# XMeter.net
KiCad netlist of a schematic drawn in Altium Designer
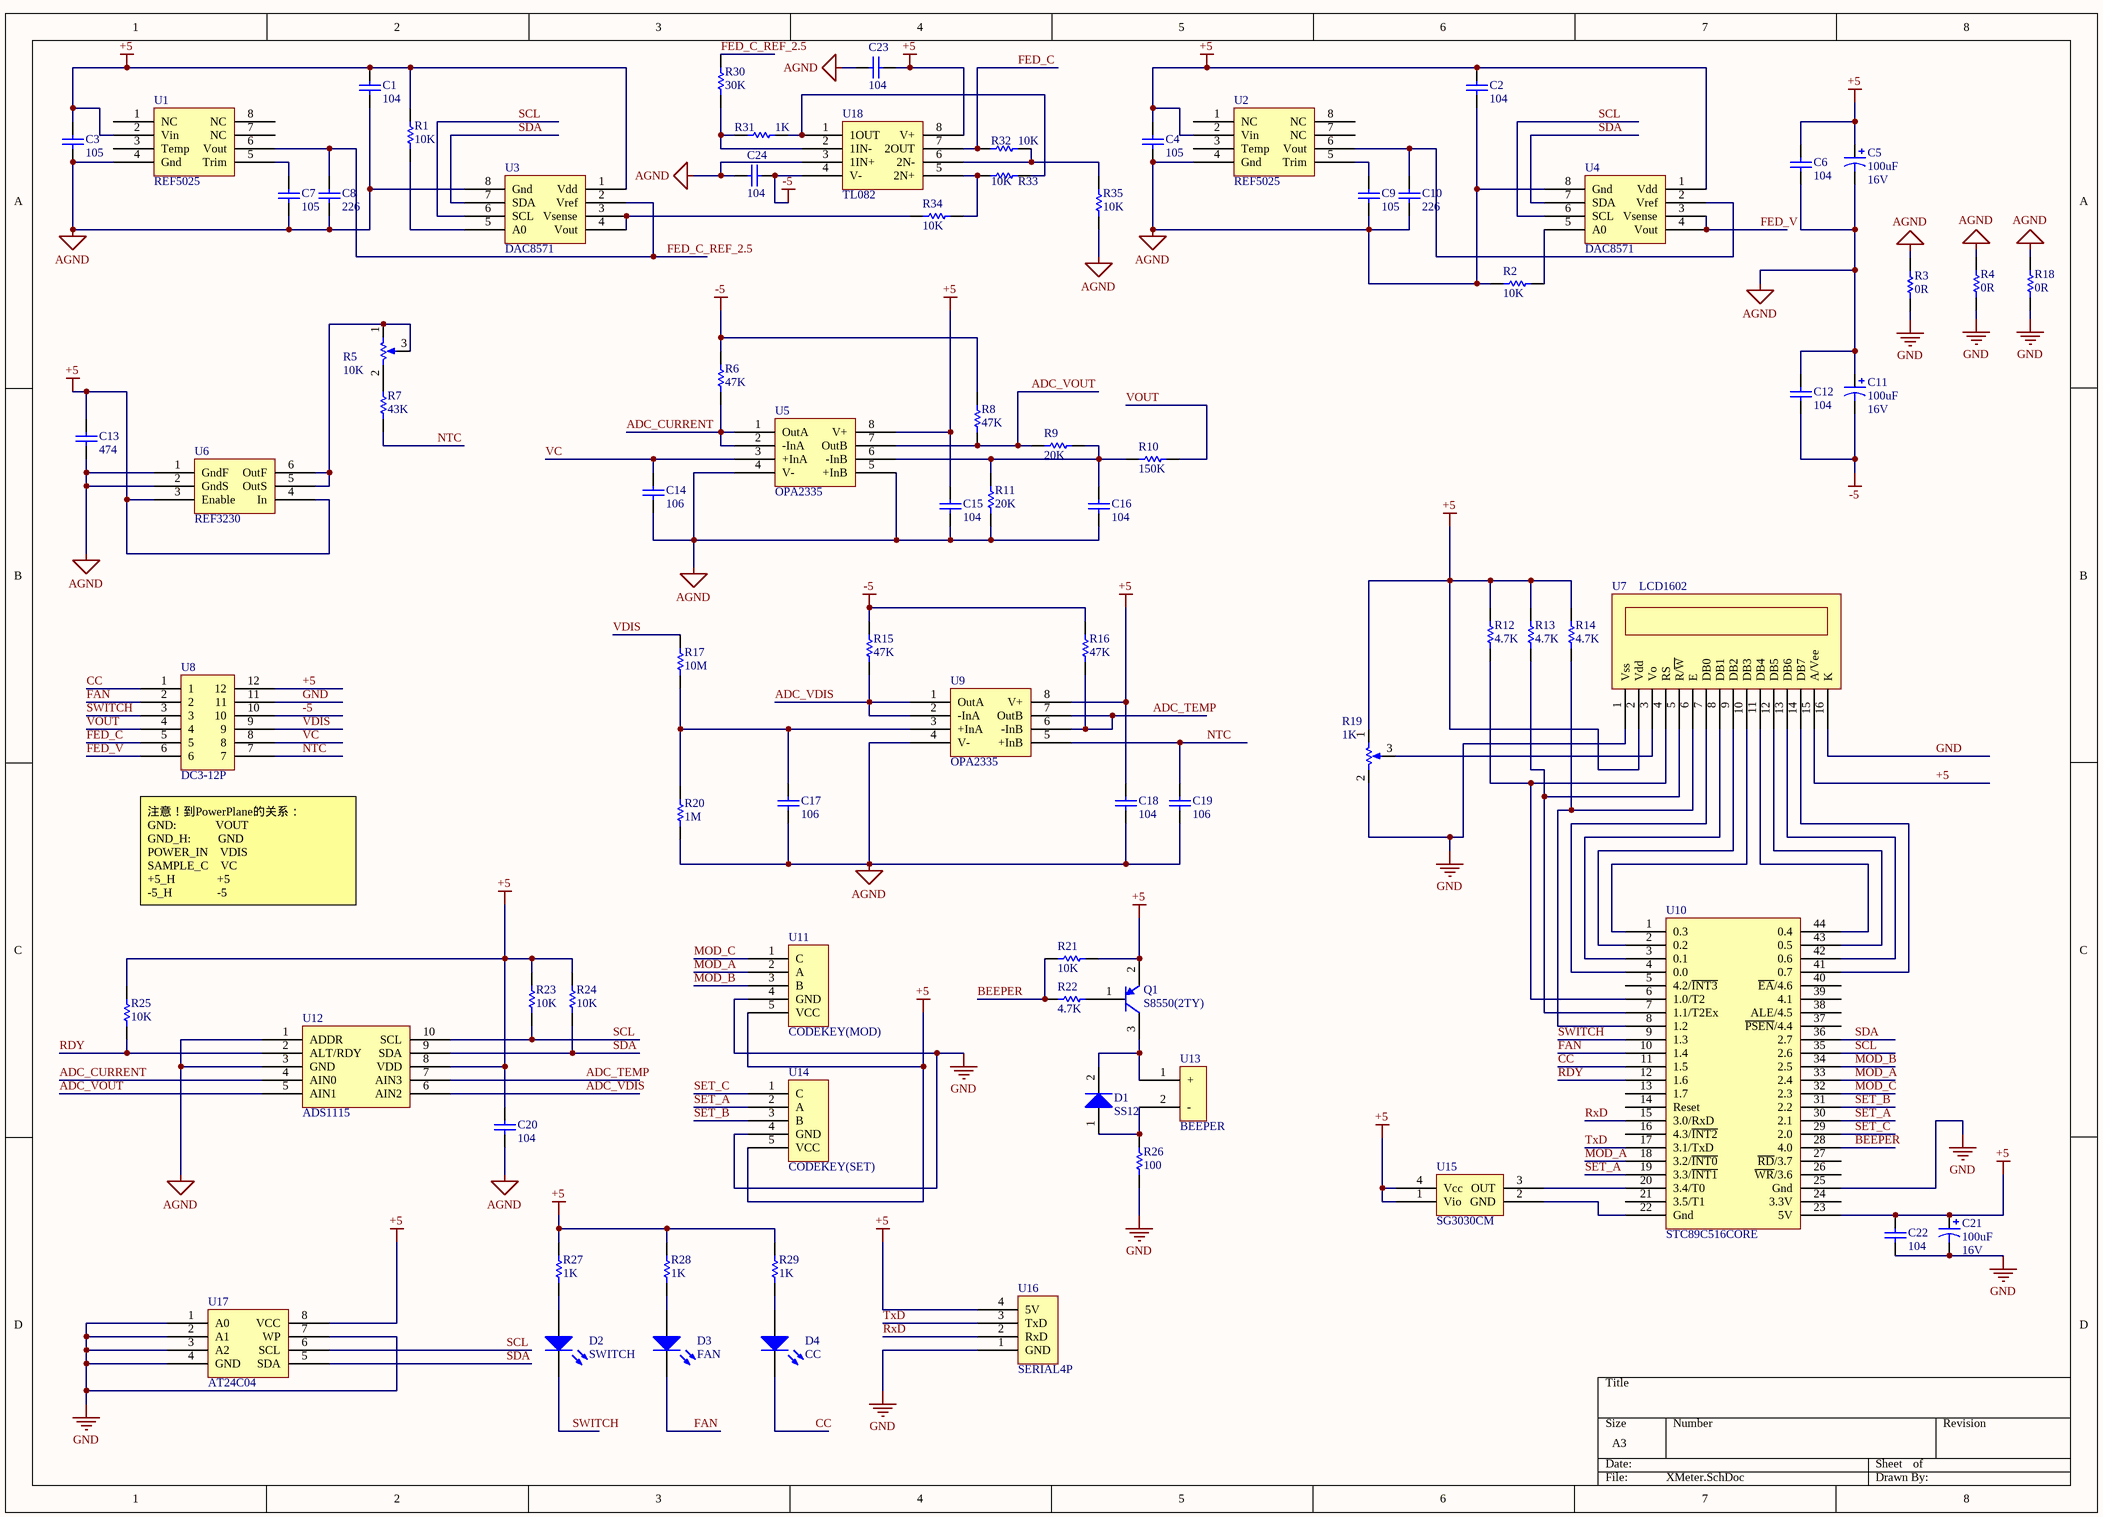
[diagram p0: XMeter.SchDoc]

(export (version "E")
  (design (tool "Eeschema 10.0.6"))
  (components
    (comp (ref "C1")
      (value "104")
      (footprint "CNCPowerSupply:CAPC1608L")
      (description "Capacitor")
      (fields (field (name "PUBLISHER") "Altium Limited"))
      (libsource (lib "Miscellaneous Devices") (part "Cap"))
    )
    (comp (ref "C2")
      (value "104")
      (footprint "CNCPowerSupply:CAPC1608L")
      (description "Capacitor")
      (fields (field (name "PUBLISHER") "Altium Limited"))
      (libsource (lib "Miscellaneous Devices") (part "Cap"))
    )
    (comp (ref "C3")
      (value "105")
      (footprint "CNCPowerSupply:CAPC1608L")
      (description "Capacitor")
      (fields (field (name "PUBLISHER") "Altium Limited"))
      (libsource (lib "Miscellaneous Devices") (part "Cap"))
    )
    (comp (ref "C4")
      (value "105")
      (footprint "CNCPowerSupply:CAPC1608L")
      (description "Capacitor")
      (fields (field (name "PUBLISHER") "Altium Limited"))
      (libsource (lib "Miscellaneous Devices") (part "Cap"))
    )
    (comp (ref "C5")
      (value "16V")
      (footprint "CNCPowerSupply:TC6032-2412")
      (description "Polarized Capacitor (Radial)")
      (fields (field (name "ALTIUM_VALUE") "100uF") (field (name "PUBLISHER") "Altium Limited"))
      (libsource (lib "Miscellaneous Devices") (part "Cap Pol1"))
    )
    (comp (ref "C6")
      (value "104")
      (footprint "CNCPowerSupply:CAPC1608L")
      (description "Capacitor")
      (fields (field (name "PUBLISHER") "Altium Limited"))
      (libsource (lib "Miscellaneous Devices") (part "Cap"))
    )
    (comp (ref "C7")
      (value "105")
      (footprint "CNCPowerSupply:CAPC1608L")
      (description "Capacitor")
      (fields (field (name "PUBLISHER") "Altium Limited"))
      (libsource (lib "Miscellaneous Devices") (part "Cap"))
    )
    (comp (ref "C8")
      (value "226")
      (footprint "CNCPowerSupply:C1206")
      (description "Capacitor")
      (fields (field (name "PUBLISHER") "Altium Limited"))
      (libsource (lib "Miscellaneous Devices") (part "Cap"))
    )
    (comp (ref "C9")
      (value "105")
      (footprint "CNCPowerSupply:CAPC1608L")
      (description "Capacitor")
      (fields (field (name "PUBLISHER") "Altium Limited"))
      (libsource (lib "Miscellaneous Devices") (part "Cap"))
    )
    (comp (ref "C10")
      (value "226")
      (footprint "CNCPowerSupply:C1206")
      (description "Capacitor")
      (fields (field (name "PUBLISHER") "Altium Limited"))
      (libsource (lib "Miscellaneous Devices") (part "Cap"))
    )
    (comp (ref "C11")
      (value "16V")
      (footprint "CNCPowerSupply:TC6032-2412")
      (description "Polarized Capacitor (Radial)")
      (fields (field (name "ALTIUM_VALUE") "100uF") (field (name "PUBLISHER") "Altium Limited"))
      (libsource (lib "Miscellaneous Devices") (part "Cap Pol1"))
    )
    (comp (ref "C12")
      (value "104")
      (footprint "CNCPowerSupply:CAPC1608L")
      (description "Capacitor")
      (fields (field (name "PUBLISHER") "Altium Limited"))
      (libsource (lib "Miscellaneous Devices") (part "Cap"))
    )
    (comp (ref "C13")
      (value "474")
      (footprint "CNCPowerSupply:CAPC1608L")
      (description "Capacitor")
      (fields (field (name "PUBLISHER") "Altium Limited"))
      (libsource (lib "Miscellaneous Devices") (part "Cap"))
    )
    (comp (ref "C14")
      (value "106")
      (footprint "CNCPowerSupply:CAPC1608L")
      (description "Capacitor")
      (fields (field (name "PUBLISHER") "Altium Limited"))
      (libsource (lib "Miscellaneous Devices") (part "Cap"))
    )
    (comp (ref "C15")
      (value "104")
      (footprint "CNCPowerSupply:CAPC1608L")
      (description "Capacitor")
      (fields (field (name "PUBLISHER") "Altium Limited"))
      (libsource (lib "Miscellaneous Devices") (part "Cap"))
    )
    (comp (ref "C16")
      (value "104")
      (footprint "CNCPowerSupply:CAPC1608L")
      (description "Capacitor")
      (fields (field (name "PUBLISHER") "Altium Limited"))
      (libsource (lib "Miscellaneous Devices") (part "Cap"))
    )
    (comp (ref "C17")
      (value "106")
      (footprint "CNCPowerSupply:CAPC1608L")
      (description "Capacitor")
      (fields (field (name "PUBLISHER") "Altium Limited"))
      (libsource (lib "Miscellaneous Devices") (part "Cap"))
    )
    (comp (ref "C18")
      (value "104")
      (footprint "CNCPowerSupply:CAPC1608L")
      (description "Capacitor")
      (fields (field (name "PUBLISHER") "Altium Limited"))
      (libsource (lib "Miscellaneous Devices") (part "Cap"))
    )
    (comp (ref "C19")
      (value "106")
      (footprint "CNCPowerSupply:CAPC1608L")
      (description "Capacitor")
      (fields (field (name "PUBLISHER") "Altium Limited"))
      (libsource (lib "Miscellaneous Devices") (part "Cap"))
    )
    (comp (ref "C20")
      (value "104")
      (footprint "CNCPowerSupply:CAPC1608L")
      (description "Capacitor")
      (fields (field (name "PUBLISHER") "Altium Limited"))
      (libsource (lib "Miscellaneous Devices") (part "Cap"))
    )
    (comp (ref "C21")
      (value "16V")
      (footprint "CNCPowerSupply:TC6032-2412")
      (description "Polarized Capacitor (Radial)")
      (fields (field (name "ALTIUM_VALUE") "100uF") (field (name "PUBLISHER") "Altium Limited"))
      (libsource (lib "Miscellaneous Devices") (part "Cap Pol1"))
    )
    (comp (ref "C22")
      (value "104")
      (footprint "CNCPowerSupply:CAPC1608L")
      (description "Capacitor")
      (fields (field (name "PUBLISHER") "Altium Limited"))
      (libsource (lib "Miscellaneous Devices") (part "Cap"))
    )
    (comp (ref "C23")
      (value "104")
      (footprint "CNCPowerSupply:CAPC1608L")
      (description "Capacitor")
      (fields (field (name "PUBLISHER") "Altium Limited"))
      (libsource (lib "Miscellaneous Devices") (part "Cap"))
    )
    (comp (ref "C24")
      (value "104")
      (footprint "CNCPowerSupply:CAPC1608L")
      (description "Capacitor")
      (fields (field (name "PUBLISHER") "Altium Limited"))
      (libsource (lib "Miscellaneous Devices") (part "Cap"))
    )
    (comp (ref "D1")
      (value "SS12")
      (footprint "CNCPowerSupply:DO214AC SMA")
      (description "1 Amp General Purpose Rectifier")
      (fields (field (name "PUBLISHER") "Altium Limited"))
      (libsource (lib "Miscellaneous Devices") (part "Diode 1N4007"))
    )
    (comp (ref "D2")
      (value "SWITCH")
      (footprint "CNCPowerSupply:LED")
      (description "Typical RED GaAs LED")
      (fields (field (name "PUBLISHER") "Altium Limited"))
      (libsource (lib "Miscellaneous Devices") (part "LED1"))
    )
    (comp (ref "D3")
      (value "FAN")
      (footprint "CNCPowerSupply:LED")
      (description "Typical RED GaAs LED")
      (fields (field (name "PUBLISHER") "Altium Limited"))
      (libsource (lib "Miscellaneous Devices") (part "LED1"))
    )
    (comp (ref "D4")
      (value "CC")
      (footprint "CNCPowerSupply:LED")
      (description "Typical RED GaAs LED")
      (fields (field (name "PUBLISHER") "Altium Limited"))
      (libsource (lib "Miscellaneous Devices") (part "LED1"))
    )
    (comp (ref "Q1")
      (value "S8550(2TY)")
      (footprint "CNCPowerSupply:SOT-23B_L")
      (description "PNP Bipolar Transistor")
      (fields (field (name "PUBLISHER") "Altium Limited"))
      (libsource (lib "Miscellaneous Devices") (part "PNP"))
    )
    (comp (ref "R1")
      (value "10K")
      (footprint "CNCPowerSupply:RESC1608L")
      (description "Resistor")
      (fields (field (name "PUBLISHER") "Altium Limited"))
      (libsource (lib "Miscellaneous Devices") (part "Res1"))
    )
    (comp (ref "R2")
      (value "10K")
      (footprint "CNCPowerSupply:RESC1608L")
      (description "Resistor")
      (fields (field (name "PUBLISHER") "Altium Limited"))
      (libsource (lib "Miscellaneous Devices") (part "Res1"))
    )
    (comp (ref "R3")
      (value "0R")
      (footprint "CNCPowerSupply:RESC1608L")
      (description "Resistor")
      (fields (field (name "PUBLISHER") "Altium Limited"))
      (libsource (lib "Miscellaneous Devices") (part "Res1"))
    )
    (comp (ref "R4")
      (value "0R")
      (footprint "CNCPowerSupply:RESC1608L")
      (description "Resistor")
      (fields (field (name "PUBLISHER") "Altium Limited"))
      (libsource (lib "Miscellaneous Devices") (part "Res1"))
    )
    (comp (ref "R5")
      (value "10K")
      (footprint "CNCPowerSupply:VR5")
      (description "Potentiometer")
      (fields (field (name "PUBLISHER") "Altium Limited"))
      (libsource (lib "Miscellaneous Devices") (part "RPot"))
    )
    (comp (ref "R6")
      (value "47K")
      (footprint "CNCPowerSupply:RESC1608L")
      (description "Resistor")
      (fields (field (name "PUBLISHER") "Altium Limited"))
      (libsource (lib "Miscellaneous Devices") (part "Res1"))
    )
    (comp (ref "R7")
      (value "43K")
      (footprint "CNCPowerSupply:RESC1608L")
      (description "Resistor")
      (fields (field (name "PUBLISHER") "Altium Limited"))
      (libsource (lib "Miscellaneous Devices") (part "Res1"))
    )
    (comp (ref "R8")
      (value "47K")
      (footprint "CNCPowerSupply:RESC1608L")
      (description "Resistor")
      (fields (field (name "PUBLISHER") "Altium Limited"))
      (libsource (lib "Miscellaneous Devices") (part "Res1"))
    )
    (comp (ref "R9")
      (value "20K")
      (footprint "CNCPowerSupply:RESC1608L")
      (description "Resistor")
      (fields (field (name "PUBLISHER") "Altium Limited"))
      (libsource (lib "Miscellaneous Devices") (part "Res1"))
    )
    (comp (ref "R10")
      (value "150K")
      (footprint "CNCPowerSupply:RESC1608L")
      (description "Resistor")
      (fields (field (name "PUBLISHER") "Altium Limited"))
      (libsource (lib "Miscellaneous Devices") (part "Res1"))
    )
    (comp (ref "R11")
      (value "20K")
      (footprint "CNCPowerSupply:RESC1608L")
      (description "Resistor")
      (fields (field (name "PUBLISHER") "Altium Limited"))
      (libsource (lib "Miscellaneous Devices") (part "Res1"))
    )
    (comp (ref "R12")
      (value "4.7K")
      (footprint "CNCPowerSupply:RESC1608L")
      (description "Resistor")
      (fields (field (name "PUBLISHER") "Altium Limited"))
      (libsource (lib "Miscellaneous Devices") (part "Res1"))
    )
    (comp (ref "R13")
      (value "4.7K")
      (footprint "CNCPowerSupply:RESC1608L")
      (description "Resistor")
      (fields (field (name "PUBLISHER") "Altium Limited"))
      (libsource (lib "Miscellaneous Devices") (part "Res1"))
    )
    (comp (ref "R14")
      (value "4.7K")
      (footprint "CNCPowerSupply:RESC1608L")
      (description "Resistor")
      (fields (field (name "PUBLISHER") "Altium Limited"))
      (libsource (lib "Miscellaneous Devices") (part "Res1"))
    )
    (comp (ref "R15")
      (value "47K")
      (footprint "CNCPowerSupply:RESC1608L")
      (description "Resistor")
      (fields (field (name "PUBLISHER") "Altium Limited"))
      (libsource (lib "Miscellaneous Devices") (part "Res1"))
    )
    (comp (ref "R16")
      (value "47K")
      (footprint "CNCPowerSupply:RESC1608L")
      (description "Resistor")
      (fields (field (name "PUBLISHER") "Altium Limited"))
      (libsource (lib "Miscellaneous Devices") (part "Res1"))
    )
    (comp (ref "R17")
      (value "10M")
      (footprint "CNCPowerSupply:RESC1608L")
      (description "Resistor")
      (fields (field (name "PUBLISHER") "Altium Limited"))
      (libsource (lib "Miscellaneous Devices") (part "Res1"))
    )
    (comp (ref "R18")
      (value "0R")
      (footprint "CNCPowerSupply:RESC1608L")
      (description "Resistor")
      (fields (field (name "PUBLISHER") "Altium Limited"))
      (libsource (lib "Miscellaneous Devices") (part "Res1"))
    )
    (comp (ref "R19")
      (value "1K")
      (footprint "CNCPowerSupply:VR4")
      (description "Potentiometer")
      (fields (field (name "PUBLISHER") "Altium Limited"))
      (libsource (lib "Miscellaneous Devices") (part "RPot"))
    )
    (comp (ref "R20")
      (value "1M")
      (footprint "CNCPowerSupply:RESC1608L")
      (description "Resistor")
      (fields (field (name "PUBLISHER") "Altium Limited"))
      (libsource (lib "Miscellaneous Devices") (part "Res1"))
    )
    (comp (ref "R21")
      (value "10K")
      (footprint "CNCPowerSupply:RESC1608L")
      (description "Resistor")
      (fields (field (name "PUBLISHER") "Altium Limited"))
      (libsource (lib "Miscellaneous Devices") (part "Res1"))
    )
    (comp (ref "R22")
      (value "4.7K")
      (footprint "CNCPowerSupply:RESC1608L")
      (description "Resistor")
      (fields (field (name "PUBLISHER") "Altium Limited"))
      (libsource (lib "Miscellaneous Devices") (part "Res1"))
    )
    (comp (ref "R23")
      (value "10K")
      (footprint "CNCPowerSupply:RESC1608L")
      (description "Resistor")
      (fields (field (name "PUBLISHER") "Altium Limited"))
      (libsource (lib "Miscellaneous Devices") (part "Res1"))
    )
    (comp (ref "R24")
      (value "10K")
      (footprint "CNCPowerSupply:RESC1608L")
      (description "Resistor")
      (fields (field (name "PUBLISHER") "Altium Limited"))
      (libsource (lib "Miscellaneous Devices") (part "Res1"))
    )
    (comp (ref "R25")
      (value "10K")
      (footprint "CNCPowerSupply:RESC1608L")
      (description "Resistor")
      (fields (field (name "PUBLISHER") "Altium Limited"))
      (libsource (lib "Miscellaneous Devices") (part "Res1"))
    )
    (comp (ref "R26")
      (value "100")
      (footprint "CNCPowerSupply:RESC1608L")
      (description "Resistor")
      (fields (field (name "PUBLISHER") "Altium Limited"))
      (libsource (lib "Miscellaneous Devices") (part "Res1"))
    )
    (comp (ref "R27")
      (value "1K")
      (footprint "CNCPowerSupply:RESC1608L")
      (description "Resistor")
      (fields (field (name "PUBLISHER") "Altium Limited"))
      (libsource (lib "Miscellaneous Devices") (part "Res1"))
    )
    (comp (ref "R28")
      (value "1K")
      (footprint "CNCPowerSupply:RESC1608L")
      (description "Resistor")
      (fields (field (name "PUBLISHER") "Altium Limited"))
      (libsource (lib "Miscellaneous Devices") (part "Res1"))
    )
    (comp (ref "R29")
      (value "1K")
      (footprint "CNCPowerSupply:RESC1608L")
      (description "Resistor")
      (fields (field (name "PUBLISHER") "Altium Limited"))
      (libsource (lib "Miscellaneous Devices") (part "Res1"))
    )
    (comp (ref "R30")
      (value "30K")
      (footprint "CNCPowerSupply:RESC1608L")
      (description "Resistor")
      (fields (field (name "PUBLISHER") "Altium Limited"))
      (libsource (lib "Miscellaneous Devices") (part "Res1"))
    )
    (comp (ref "R31")
      (value "1K")
      (footprint "CNCPowerSupply:RESC1608L")
      (description "Resistor")
      (fields (field (name "PUBLISHER") "Altium Limited"))
      (libsource (lib "Miscellaneous Devices") (part "Res1"))
    )
    (comp (ref "R32")
      (value "10K")
      (footprint "CNCPowerSupply:RESC1608L")
      (description "Resistor")
      (fields (field (name "PUBLISHER") "Altium Limited"))
      (libsource (lib "Miscellaneous Devices") (part "Res1"))
    )
    (comp (ref "R33")
      (value "10K")
      (footprint "CNCPowerSupply:RESC1608L")
      (description "Resistor")
      (fields (field (name "PUBLISHER") "Altium Limited"))
      (libsource (lib "Miscellaneous Devices") (part "Res1"))
    )
    (comp (ref "R34")
      (value "10K")
      (footprint "CNCPowerSupply:RESC1608L")
      (description "Resistor")
      (fields (field (name "PUBLISHER") "Altium Limited"))
      (libsource (lib "Miscellaneous Devices") (part "Res1"))
    )
    (comp (ref "R35")
      (value "10K")
      (footprint "CNCPowerSupply:RESC1608L")
      (description "Resistor")
      (fields (field (name "PUBLISHER") "Altium Limited"))
      (libsource (lib "Miscellaneous Devices") (part "Res1"))
    )
    (comp (ref "U1")
      (value "REF5025")
      (footprint "CNCPowerSupply:SOP127P636-8L")
      (libsource (lib "CNCPowerSupply") (part "REF5025"))
    )
    (comp (ref "U2")
      (value "REF5025")
      (footprint "CNCPowerSupply:SOP127P636-8L")
      (libsource (lib "CNCPowerSupply") (part "REF5025"))
    )
    (comp (ref "U3")
      (value "DAC8571")
      (footprint "CNCPowerSupply:TSOP65P490-8AL")
      (libsource (lib "CNCPowerSupply") (part "DAC8571"))
    )
    (comp (ref "U4")
      (value "DAC8571")
      (footprint "CNCPowerSupply:TSOP65P490-8AL")
      (libsource (lib "CNCPowerSupply") (part "DAC8571"))
    )
    (comp (ref "U5")
      (value "OPA2335")
      (footprint "CNCPowerSupply:SOP127P636-8L")
      (libsource (lib "CNCPowerSupply") (part "OPA2335"))
    )
    (comp (ref "U6")
      (value "REF3230")
      (footprint "CNCPowerSupply:SOT26A-6L")
      (libsource (lib "CNCPowerSupply") (part "REF3230"))
    )
    (comp (ref "U7")
      (value "LCD1602")
      (footprint "CNCPowerSupply:LCD1602")
      (libsource (lib "CNCPowerSupply") (part "LCD1602"))
    )
    (comp (ref "U8")
      (value "DC3-12P")
      (footprint "CNCPowerSupply:DC3-12P")
      (libsource (lib "CNCPowerSupply") (part "DC3-12P"))
    )
    (comp (ref "U9")
      (value "OPA2335")
      (footprint "CNCPowerSupply:SOP127P636-8L")
      (libsource (lib "CNCPowerSupply") (part "OPA2335"))
    )
    (comp (ref "U10")
      (value "STC89C516CORE")
      (footprint "CNCPowerSupply:STC89516CORE")
      (libsource (lib "CNCPowerSupply") (part "STC89C516CORE"))
    )
    (comp (ref "U11")
      (value "CODEKEY(MOD)")
      (footprint "CNCPowerSupply:CODEKEY")
      (description "CODEKEY")
      (libsource (lib "CNCPowerSupply") (part "CODEKEY"))
    )
    (comp (ref "U12")
      (value "ADS1115")
      (footprint "CNCPowerSupply:TSSOP50P490-10AL")
      (libsource (lib "CNCPowerSupply") (part "ADS1115"))
    )
    (comp (ref "U13")
      (value "BEEPER")
      (footprint "CNCPowerSupply:BEEPER")
      (libsource (lib "CNCPowerSupply") (part "BEEPER"))
    )
    (comp (ref "U14")
      (value "CODEKEY(SET)")
      (footprint "CNCPowerSupply:CODEKEY")
      (description "CODEKEY")
      (libsource (lib "CNCPowerSupply") (part "CODEKEY"))
    )
    (comp (ref "U15")
      (value "SG3030CM")
      (footprint "CNCPowerSupply:SG3030CM")
      (libsource (lib "CNCPowerSupply") (part "SG3030CM"))
    )
    (comp (ref "U16")
      (value "SERIAL4P")
      (footprint "CNCPowerSupply:X254-4P")
      (libsource (lib "CNCPowerSupply") (part "SERIAL4P"))
    )
    (comp (ref "U17")
      (value "AT24C04")
      (footprint "CNCPowerSupply:DIP-8")
      (libsource (lib "CNCPowerSupply") (part "AT24C04"))
    )
    (comp (ref "U18")
      (value "TL082")
      (footprint "CNCPowerSupply:DIP-8")
      (libsource (lib "CNCPowerSupply") (part "TL082"))
    )
  )
  (nets
    (net (code "1") (name "+5") (class "Default")
      (node (ref "C1") (pin "2") (pinfunction "2_2") (pintype "passive"))
      (node (ref "C13") (pin "2") (pinfunction "2_2") (pintype "passive"))
      (node (ref "C15") (pin "2") (pinfunction "2_2") (pintype "passive"))
      (node (ref "C18") (pin "2") (pinfunction "2_2") (pintype "passive"))
      (node (ref "C2") (pin "2") (pinfunction "2_2") (pintype "passive"))
      (node (ref "C20") (pin "2") (pinfunction "2_2") (pintype "passive"))
      (node (ref "C21") (pin "1") (pinfunction "1_1") (pintype "passive"))
      (node (ref "C22") (pin "2") (pinfunction "2_2") (pintype "passive"))
      (node (ref "C23") (pin "1") (pinfunction "1_1") (pintype "passive"))
      (node (ref "C3") (pin "2") (pinfunction "2_2") (pintype "passive"))
      (node (ref "C4") (pin "2") (pinfunction "2_2") (pintype "passive"))
      (node (ref "C5") (pin "1") (pinfunction "1_1") (pintype "passive"))
      (node (ref "C6") (pin "2") (pinfunction "2_2") (pintype "passive"))
      (node (ref "Q1") (pin "2") (pinfunction "E_2") (pintype "passive"))
      (node (ref "R1") (pin "1") (pinfunction "1_1") (pintype "passive"))
      (node (ref "R12") (pin "1") (pinfunction "1_1") (pintype "passive"))
      (node (ref "R13") (pin "1") (pinfunction "1_1") (pintype "passive"))
      (node (ref "R14") (pin "1") (pinfunction "1_1") (pintype "passive"))
      (node (ref "R19") (pin "1") (pinfunction "TOP_1") (pintype "passive"))
      (node (ref "R21") (pin "2") (pinfunction "2_2") (pintype "passive"))
      (node (ref "R23") (pin "1") (pinfunction "1_1") (pintype "passive"))
      (node (ref "R24") (pin "1") (pinfunction "1_1") (pintype "passive"))
      (node (ref "R25") (pin "1") (pinfunction "1_1") (pintype "passive"))
      (node (ref "R27") (pin "2") (pinfunction "2_2") (pintype "passive"))
      (node (ref "R28") (pin "2") (pinfunction "2_2") (pintype "passive"))
      (node (ref "R29") (pin "2") (pinfunction "2_2") (pintype "passive"))
      (node (ref "U1") (pin "2") (pinfunction "Vin_2") (pintype "passive"))
      (node (ref "U10") (pin "23") (pinfunction "5V_23") (pintype "passive"))
      (node (ref "U11") (pin "5") (pinfunction "VCC_5") (pintype "passive"))
      (node (ref "U12") (pin "8") (pinfunction "VDD_8") (pintype "passive"))
      (node (ref "U14") (pin "5") (pinfunction "VCC_5") (pintype "passive"))
      (node (ref "U15") (pin "1") (pinfunction "Vio_1") (pintype "passive"))
      (node (ref "U15") (pin "4") (pinfunction "Vcc_4") (pintype "passive"))
      (node (ref "U16") (pin "4") (pinfunction "5V_4") (pintype "passive"))
      (node (ref "U17") (pin "8") (pinfunction "VCC_8") (pintype "passive"))
      (node (ref "U18") (pin "8") (pinfunction "V+_8") (pintype "passive"))
      (node (ref "U2") (pin "2") (pinfunction "Vin_2") (pintype "passive"))
      (node (ref "U3") (pin "1") (pinfunction "Vdd_1") (pintype "passive"))
      (node (ref "U4") (pin "1") (pinfunction "Vdd_1") (pintype "passive"))
      (node (ref "U5") (pin "8") (pinfunction "V+_8") (pintype "passive"))
      (node (ref "U6") (pin "3") (pinfunction "Enable_3") (pintype "passive"))
      (node (ref "U6") (pin "4") (pinfunction "In_4") (pintype "passive"))
      (node (ref "U7") (pin "15") (pinfunction "A/Vee_15") (pintype "passive"))
      (node (ref "U7") (pin "2") (pinfunction "Vdd_2") (pintype "passive"))
      (node (ref "U8") (pin "12") (pinfunction "12_12") (pintype "passive"))
      (node (ref "U9") (pin "8") (pinfunction "V+_8") (pintype "passive"))
    )
    (net (code "2") (name "-5") (class "Default")
      (node (ref "C11") (pin "2") (pinfunction "2_2") (pintype "passive"))
      (node (ref "C12") (pin "1") (pinfunction "1_1") (pintype "passive"))
      (node (ref "C24") (pin "1") (pinfunction "1_1") (pintype "passive"))
      (node (ref "R15") (pin "1") (pinfunction "1_1") (pintype "passive"))
      (node (ref "R16") (pin "1") (pinfunction "1_1") (pintype "passive"))
      (node (ref "R6") (pin "1") (pinfunction "1_1") (pintype "passive"))
      (node (ref "R8") (pin "1") (pinfunction "1_1") (pintype "passive"))
      (node (ref "U18") (pin "4") (pinfunction "V-_4") (pintype "passive"))
      (node (ref "U8") (pin "10") (pinfunction "10_10") (pintype "passive"))
    )
    (net (code "3") (name "/ADC_CURRENT") (class "Default")
      (node (ref "R6") (pin "2") (pinfunction "2_2") (pintype "passive"))
      (node (ref "U12") (pin "4") (pinfunction "AIN0_4") (pintype "passive"))
      (node (ref "U5") (pin "1") (pinfunction "OutA_1") (pintype "passive"))
      (node (ref "U5") (pin "2") (pinfunction "-InA_2") (pintype "passive"))
    )
    (net (code "4") (name "/ADC_TEMP") (class "Default")
      (node (ref "R16") (pin "2") (pinfunction "2_2") (pintype "passive"))
      (node (ref "U12") (pin "7") (pinfunction "AIN3_7") (pintype "passive"))
      (node (ref "U9") (pin "6") (pinfunction "-InB_6") (pintype "passive"))
      (node (ref "U9") (pin "7") (pinfunction "OutB_7") (pintype "passive"))
    )
    (net (code "5") (name "/ADC_VDIS") (class "Default")
      (node (ref "R15") (pin "2") (pinfunction "2_2") (pintype "passive"))
      (node (ref "U12") (pin "6") (pinfunction "AIN2_6") (pintype "passive"))
      (node (ref "U9") (pin "1") (pinfunction "OutA_1") (pintype "passive"))
      (node (ref "U9") (pin "2") (pinfunction "-InA_2") (pintype "passive"))
    )
    (net (code "6") (name "/ADC_VOUT") (class "Default")
      (node (ref "R8") (pin "2") (pinfunction "2_2") (pintype "passive"))
      (node (ref "R9") (pin "1") (pinfunction "1_1") (pintype "passive"))
      (node (ref "U12") (pin "5") (pinfunction "AIN1_5") (pintype "passive"))
      (node (ref "U5") (pin "7") (pinfunction "OutB_7") (pintype "passive"))
    )
    (net (code "7") (name "/BEEPER") (class "Default")
      (node (ref "R21") (pin "1") (pinfunction "1_1") (pintype "passive"))
      (node (ref "R22") (pin "1") (pinfunction "1_1") (pintype "passive"))
      (node (ref "U10") (pin "28") (pinfunction "4.0_28") (pintype "passive"))
    )
    (net (code "8") (name "/CC") (class "Default")
      (node (ref "D4") (pin "2") (pinfunction "K_2") (pintype "passive"))
      (node (ref "U10") (pin "11") (pinfunction "1.5_11") (pintype "passive"))
      (node (ref "U8") (pin "1") (pinfunction "1_1") (pintype "passive"))
    )
    (net (code "9") (name "/FAN") (class "Default")
      (node (ref "D3") (pin "2") (pinfunction "K_2") (pintype "passive"))
      (node (ref "U10") (pin "10") (pinfunction "1.4_10") (pintype "passive"))
      (node (ref "U8") (pin "2") (pinfunction "2_2") (pintype "passive"))
    )
    (net (code "10") (name "/FED_C") (class "Default")
      (node (ref "R32") (pin "1") (pinfunction "1_1") (pintype "passive"))
      (node (ref "U18") (pin "7") (pinfunction "2OUT_7") (pintype "passive"))
      (node (ref "U8") (pin "5") (pinfunction "5_5") (pintype "passive"))
    )
    (net (code "11") (name "/FED_C_REF_2.5") (class "Default")
      (node (ref "C8") (pin "1") (pinfunction "1_1") (pintype "passive"))
      (node (ref "R30") (pin "2") (pinfunction "2_2") (pintype "passive"))
      (node (ref "U1") (pin "6") (pinfunction "Vout_6") (pintype "passive"))
      (node (ref "U3") (pin "2") (pinfunction "Vref_2") (pintype "passive"))
    )
    (net (code "12") (name "/FED_V") (class "Default")
      (node (ref "U4") (pin "3") (pinfunction "Vsense_3") (pintype "passive"))
      (node (ref "U4") (pin "4") (pinfunction "Vout_4") (pintype "passive"))
      (node (ref "U8") (pin "6") (pinfunction "6_6") (pintype "passive"))
    )
    (net (code "13") (name "/MOD_A") (class "Default")
      (node (ref "U10") (pin "18") (pinfunction "3.2/~{INT0}_18") (pintype "passive"))
      (node (ref "U10") (pin "33") (pinfunction "2.4_33") (pintype "passive"))
      (node (ref "U11") (pin "2") (pinfunction "A_2") (pintype "passive"))
    )
    (net (code "14") (name "/MOD_B") (class "Default")
      (node (ref "U10") (pin "34") (pinfunction "2.5_34") (pintype "passive"))
      (node (ref "U11") (pin "3") (pinfunction "B_3") (pintype "passive"))
    )
    (net (code "15") (name "/MOD_C") (class "Default")
      (node (ref "U10") (pin "32") (pinfunction "2.3_32") (pintype "passive"))
      (node (ref "U11") (pin "1") (pinfunction "C_1") (pintype "passive"))
    )
    (net (code "16") (name "/NTC") (class "Default")
      (node (ref "C19") (pin "2") (pinfunction "2_2") (pintype "passive"))
      (node (ref "R7") (pin "2") (pinfunction "2_2") (pintype "passive"))
      (node (ref "U8") (pin "7") (pinfunction "7_7") (pintype "passive"))
      (node (ref "U9") (pin "5") (pinfunction "+InB_5") (pintype "passive"))
    )
    (net (code "17") (name "/RDY") (class "Default")
      (node (ref "R25") (pin "2") (pinfunction "2_2") (pintype "passive"))
      (node (ref "U10") (pin "12") (pinfunction "1.6_12") (pintype "passive"))
      (node (ref "U12") (pin "2") (pinfunction "ALT/RDY_2") (pintype "passive"))
    )
    (net (code "18") (name "/RxD") (class "Default")
      (node (ref "U10") (pin "15") (pinfunction "3.0/RxD_15") (pintype "passive"))
      (node (ref "U16") (pin "2") (pinfunction "RxD_2") (pintype "passive"))
    )
    (net (code "19") (name "/SCL") (class "Default")
      (node (ref "R23") (pin "2") (pinfunction "2_2") (pintype "passive"))
      (node (ref "U10") (pin "35") (pinfunction "2.6_35") (pintype "passive"))
      (node (ref "U12") (pin "10") (pinfunction "SCL_10") (pintype "passive"))
      (node (ref "U17") (pin "6") (pinfunction "SCL_6") (pintype "passive"))
      (node (ref "U3") (pin "6") (pinfunction "SCL_6") (pintype "passive"))
      (node (ref "U4") (pin "6") (pinfunction "SCL_6") (pintype "passive"))
    )
    (net (code "20") (name "/SDA") (class "Default")
      (node (ref "R24") (pin "2") (pinfunction "2_2") (pintype "passive"))
      (node (ref "U10") (pin "36") (pinfunction "2.7_36") (pintype "passive"))
      (node (ref "U12") (pin "9") (pinfunction "SDA_9") (pintype "passive"))
      (node (ref "U17") (pin "5") (pinfunction "SDA_5") (pintype "passive"))
      (node (ref "U3") (pin "7") (pinfunction "SDA_7") (pintype "passive"))
      (node (ref "U4") (pin "7") (pinfunction "SDA_7") (pintype "passive"))
    )
    (net (code "21") (name "/SET_A") (class "Default")
      (node (ref "U10") (pin "19") (pinfunction "3.3/~{INT1}_19") (pintype "passive"))
      (node (ref "U10") (pin "30") (pinfunction "2.1_30") (pintype "passive"))
      (node (ref "U14") (pin "2") (pinfunction "A_2") (pintype "passive"))
    )
    (net (code "22") (name "/SET_B") (class "Default")
      (node (ref "U10") (pin "31") (pinfunction "2.2_31") (pintype "passive"))
      (node (ref "U14") (pin "3") (pinfunction "B_3") (pintype "passive"))
    )
    (net (code "23") (name "/SET_C") (class "Default")
      (node (ref "U10") (pin "29") (pinfunction "2.0_29") (pintype "passive"))
      (node (ref "U14") (pin "1") (pinfunction "C_1") (pintype "passive"))
    )
    (net (code "24") (name "/SWITCH") (class "Default")
      (node (ref "D2") (pin "2") (pinfunction "K_2") (pintype "passive"))
      (node (ref "U10") (pin "9") (pinfunction "1.3_9") (pintype "passive"))
      (node (ref "U8") (pin "3") (pinfunction "3_3") (pintype "passive"))
    )
    (net (code "25") (name "/TxD") (class "Default")
      (node (ref "U10") (pin "17") (pinfunction "3.1/TxD_17") (pintype "passive"))
      (node (ref "U16") (pin "3") (pinfunction "TxD_3") (pintype "passive"))
    )
    (net (code "26") (name "/VC") (class "Default")
      (node (ref "C14") (pin "2") (pinfunction "2_2") (pintype "passive"))
      (node (ref "U5") (pin "3") (pinfunction "+InA_3") (pintype "passive"))
      (node (ref "U8") (pin "8") (pinfunction "8_8") (pintype "passive"))
    )
    (net (code "27") (name "/VDIS") (class "Default")
      (node (ref "R17") (pin "1") (pinfunction "1_1") (pintype "passive"))
      (node (ref "U8") (pin "9") (pinfunction "9_9") (pintype "passive"))
    )
    (net (code "28") (name "/VOUT") (class "Default")
      (node (ref "R10") (pin "2") (pinfunction "2_2") (pintype "passive"))
      (node (ref "U8") (pin "4") (pinfunction "4_4") (pintype "passive"))
    )
    (net (code "29") (name "AGND") (class "Default")
      (node (ref "C1") (pin "1") (pinfunction "1_1") (pintype "passive"))
      (node (ref "C10") (pin "2") (pinfunction "2_2") (pintype "passive"))
      (node (ref "C11") (pin "1") (pinfunction "1_1") (pintype "passive"))
      (node (ref "C12") (pin "2") (pinfunction "2_2") (pintype "passive"))
      (node (ref "C13") (pin "1") (pinfunction "1_1") (pintype "passive"))
      (node (ref "C14") (pin "1") (pinfunction "1_1") (pintype "passive"))
      (node (ref "C15") (pin "1") (pinfunction "1_1") (pintype "passive"))
      (node (ref "C16") (pin "1") (pinfunction "1_1") (pintype "passive"))
      (node (ref "C17") (pin "1") (pinfunction "1_1") (pintype "passive"))
      (node (ref "C18") (pin "1") (pinfunction "1_1") (pintype "passive"))
      (node (ref "C19") (pin "1") (pinfunction "1_1") (pintype "passive"))
      (node (ref "C2") (pin "1") (pinfunction "1_1") (pintype "passive"))
      (node (ref "C20") (pin "1") (pinfunction "1_1") (pintype "passive"))
      (node (ref "C23") (pin "2") (pinfunction "2_2") (pintype "passive"))
      (node (ref "C24") (pin "2") (pinfunction "2_2") (pintype "passive"))
      (node (ref "C3") (pin "1") (pinfunction "1_1") (pintype "passive"))
      (node (ref "C4") (pin "1") (pinfunction "1_1") (pintype "passive"))
      (node (ref "C5") (pin "2") (pinfunction "2_2") (pintype "passive"))
      (node (ref "C6") (pin "1") (pinfunction "1_1") (pintype "passive"))
      (node (ref "C7") (pin "1") (pinfunction "1_1") (pintype "passive"))
      (node (ref "C8") (pin "2") (pinfunction "2_2") (pintype "passive"))
      (node (ref "C9") (pin "1") (pinfunction "1_1") (pintype "passive"))
      (node (ref "R11") (pin "2") (pinfunction "2_2") (pintype "passive"))
      (node (ref "R18") (pin "1") (pinfunction "1_1") (pintype "passive"))
      (node (ref "R2") (pin "2") (pinfunction "2_2") (pintype "passive"))
      (node (ref "R20") (pin "2") (pinfunction "2_2") (pintype "passive"))
      (node (ref "R3") (pin "1") (pinfunction "1_1") (pintype "passive"))
      (node (ref "R35") (pin "2") (pinfunction "2_2") (pintype "passive"))
      (node (ref "R4") (pin "1") (pinfunction "1_1") (pintype "passive"))
      (node (ref "U1") (pin "4") (pinfunction "Gnd_4") (pintype "passive"))
      (node (ref "U12") (pin "1") (pinfunction "ADDR_1") (pintype "passive"))
      (node (ref "U12") (pin "3") (pinfunction "GND_3") (pintype "passive"))
      (node (ref "U18") (pin "3") (pinfunction "1IN+_3") (pintype "passive"))
      (node (ref "U2") (pin "4") (pinfunction "Gnd_4") (pintype "passive"))
      (node (ref "U3") (pin "8") (pinfunction "Gnd_8") (pintype "passive"))
      (node (ref "U4") (pin "8") (pinfunction "Gnd_8") (pintype "passive"))
      (node (ref "U5") (pin "4") (pinfunction "V-_4") (pintype "passive"))
      (node (ref "U5") (pin "5") (pinfunction "+InB_5") (pintype "passive"))
      (node (ref "U6") (pin "1") (pinfunction "GndF_1") (pintype "passive"))
      (node (ref "U6") (pin "2") (pinfunction "GndS_2") (pintype "passive"))
      (node (ref "U9") (pin "4") (pinfunction "V-_4") (pintype "passive"))
    )
    (net (code "30") (name "GND") (class "Default")
      (node (ref "C21") (pin "2") (pinfunction "2_2") (pintype "passive"))
      (node (ref "C22") (pin "1") (pinfunction "1_1") (pintype "passive"))
      (node (ref "R18") (pin "2") (pinfunction "2_2") (pintype "passive"))
      (node (ref "R19") (pin "2") (pinfunction "BOT_2") (pintype "passive"))
      (node (ref "R26") (pin "1") (pinfunction "1_1") (pintype "passive"))
      (node (ref "R3") (pin "2") (pinfunction "2_2") (pintype "passive"))
      (node (ref "R4") (pin "2") (pinfunction "2_2") (pintype "passive"))
      (node (ref "U10") (pin "25") (pinfunction "Gnd_25") (pintype "passive"))
      (node (ref "U11") (pin "4") (pinfunction "GND_4") (pintype "passive"))
      (node (ref "U14") (pin "4") (pinfunction "GND_4") (pintype "passive"))
      (node (ref "U16") (pin "1") (pinfunction "GND_1") (pintype "passive"))
      (node (ref "U17") (pin "1") (pinfunction "A0_1") (pintype "passive"))
      (node (ref "U17") (pin "2") (pinfunction "A1_2") (pintype "passive"))
      (node (ref "U17") (pin "3") (pinfunction "A2_3") (pintype "passive"))
      (node (ref "U17") (pin "4") (pinfunction "GND_4") (pintype "passive"))
      (node (ref "U17") (pin "7") (pinfunction "WP_7") (pintype "passive"))
      (node (ref "U7") (pin "1") (pinfunction "Vss_1") (pintype "passive"))
      (node (ref "U7") (pin "16") (pinfunction "K_16") (pintype "passive"))
      (node (ref "U8") (pin "11") (pinfunction "11_11") (pintype "passive"))
    )
    (net (code "31") (name "Net-(D1-A)") (class "Default")
      (node (ref "D1") (pin "1") (pinfunction "A_1") (pintype "passive"))
      (node (ref "R26") (pin "2") (pinfunction "2_2") (pintype "passive"))
      (node (ref "U13") (pin "2") (pinfunction "-_2") (pintype "passive"))
    )
    (net (code "32") (name "Net-(D1-K)") (class "Default")
      (node (ref "D1") (pin "2") (pinfunction "K_2") (pintype "passive"))
      (node (ref "Q1") (pin "3") (pinfunction "C_3") (pintype "passive"))
      (node (ref "U13") (pin "1") (pinfunction "+_1") (pintype "passive"))
    )
    (net (code "33") (name "Net-(D2-A)") (class "Default")
      (node (ref "D2") (pin "1") (pinfunction "A_1") (pintype "passive"))
      (node (ref "R27") (pin "1") (pinfunction "1_1") (pintype "passive"))
    )
    (net (code "34") (name "Net-(D3-A)") (class "Default")
      (node (ref "D3") (pin "1") (pinfunction "A_1") (pintype "passive"))
      (node (ref "R28") (pin "1") (pinfunction "1_1") (pintype "passive"))
    )
    (net (code "35") (name "Net-(D4-A)") (class "Default")
      (node (ref "D4") (pin "1") (pinfunction "A_1") (pintype "passive"))
      (node (ref "R29") (pin "1") (pinfunction "1_1") (pintype "passive"))
    )
    (net (code "36") (name "Net-(Q1-B)") (class "Default")
      (node (ref "Q1") (pin "1") (pinfunction "B_1") (pintype "passive"))
      (node (ref "R22") (pin "2") (pinfunction "2_2") (pintype "passive"))
    )
    (net (code "37") (name "Net-(R5-BOT)") (class "Default")
      (node (ref "R5") (pin "2") (pinfunction "BOT_2") (pintype "passive"))
      (node (ref "R7") (pin "1") (pinfunction "1_1") (pintype "passive"))
    )
    (net (code "38") (name "Net-(R5-TAP)") (class "Default")
      (node (ref "R5") (pin "1") (pinfunction "TOP_1") (pintype "passive"))
      (node (ref "R5") (pin "3") (pinfunction "TAP_3") (pintype "passive"))
      (node (ref "U6") (pin "5") (pinfunction "OutS_5") (pintype "passive"))
      (node (ref "U6") (pin "6") (pinfunction "OutF_6") (pintype "passive"))
    )
    (net (code "39") (name "Net-(R19-TAP)") (class "Default")
      (node (ref "R19") (pin "3") (pinfunction "TAP_3") (pintype "passive"))
      (node (ref "U7") (pin "3") (pinfunction "Vo_3") (pintype "passive"))
    )
    (net (code "40") (name "Net-(U1-Trim)") (class "Default")
      (node (ref "C7") (pin "2") (pinfunction "2_2") (pintype "passive"))
      (node (ref "U1") (pin "5") (pinfunction "Trim_5") (pintype "passive"))
    )
    (net (code "41") (name "Net-(U2-Trim)") (class "Default")
      (node (ref "C9") (pin "2") (pinfunction "2_2") (pintype "passive"))
      (node (ref "U2") (pin "5") (pinfunction "Trim_5") (pintype "passive"))
    )
    (net (code "42") (name "Net-(U2-Vout)") (class "Default")
      (node (ref "C10") (pin "1") (pinfunction "1_1") (pintype "passive"))
      (node (ref "U2") (pin "6") (pinfunction "Vout_6") (pintype "passive"))
      (node (ref "U4") (pin "2") (pinfunction "Vref_2") (pintype "passive"))
    )
    (net (code "43") (name "Net-(U3-A0)") (class "Default")
      (node (ref "R1") (pin "2") (pinfunction "2_2") (pintype "passive"))
      (node (ref "U3") (pin "5") (pinfunction "A0_5") (pintype "passive"))
    )
    (net (code "44") (name "Net-(U3-Vout)") (class "Default")
      (node (ref "R34") (pin "1") (pinfunction "1_1") (pintype "passive"))
      (node (ref "U3") (pin "3") (pinfunction "Vsense_3") (pintype "passive"))
      (node (ref "U3") (pin "4") (pinfunction "Vout_4") (pintype "passive"))
    )
    (net (code "45") (name "Net-(U4-A0)") (class "Default")
      (node (ref "R2") (pin "1") (pinfunction "1_1") (pintype "passive"))
      (node (ref "U4") (pin "5") (pinfunction "A0_5") (pintype "passive"))
    )
    (net (code "46") (name "Net-(U5--InB)") (class "Default")
      (node (ref "C16") (pin "2") (pinfunction "2_2") (pintype "passive"))
      (node (ref "R10") (pin "1") (pinfunction "1_1") (pintype "passive"))
      (node (ref "R11") (pin "1") (pinfunction "1_1") (pintype "passive"))
      (node (ref "R9") (pin "2") (pinfunction "2_2") (pintype "passive"))
      (node (ref "U5") (pin "6") (pinfunction "-InB_6") (pintype "passive"))
    )
    (net (code "47") (name "Net-(U9-+InA)") (class "Default")
      (node (ref "C17") (pin "2") (pinfunction "2_2") (pintype "passive"))
      (node (ref "R17") (pin "2") (pinfunction "2_2") (pintype "passive"))
      (node (ref "R20") (pin "1") (pinfunction "1_1") (pintype "passive"))
      (node (ref "U9") (pin "3") (pinfunction "+InA_3") (pintype "passive"))
    )
    (net (code "48") (name "Net-(U10-0.0)") (class "Default")
      (node (ref "U10") (pin "4") (pinfunction "0.0_4") (pintype "passive"))
      (node (ref "U7") (pin "7") (pinfunction "DB0_7") (pintype "passive"))
    )
    (net (code "49") (name "Net-(U10-0.1)") (class "Default")
      (node (ref "U10") (pin "3") (pinfunction "0.1_3") (pintype "passive"))
      (node (ref "U7") (pin "8") (pinfunction "DB1_8") (pintype "passive"))
    )
    (net (code "50") (name "Net-(U10-0.2)") (class "Default")
      (node (ref "U10") (pin "2") (pinfunction "0.2_2") (pintype "passive"))
      (node (ref "U7") (pin "9") (pinfunction "DB2_9") (pintype "passive"))
    )
    (net (code "51") (name "Net-(U10-0.3)") (class "Default")
      (node (ref "U10") (pin "1") (pinfunction "0.3_1") (pintype "passive"))
      (node (ref "U7") (pin "10") (pinfunction "DB3_10") (pintype "passive"))
    )
    (net (code "52") (name "Net-(U10-0.4)") (class "Default")
      (node (ref "U10") (pin "44") (pinfunction "0.4_44") (pintype "passive"))
      (node (ref "U7") (pin "11") (pinfunction "DB4_11") (pintype "passive"))
    )
    (net (code "53") (name "Net-(U10-0.5)") (class "Default")
      (node (ref "U10") (pin "43") (pinfunction "0.5_43") (pintype "passive"))
      (node (ref "U7") (pin "12") (pinfunction "DB5_12") (pintype "passive"))
    )
    (net (code "54") (name "Net-(U10-0.6)") (class "Default")
      (node (ref "U10") (pin "42") (pinfunction "0.6_42") (pintype "passive"))
      (node (ref "U7") (pin "13") (pinfunction "DB6_13") (pintype "passive"))
    )
    (net (code "55") (name "Net-(U10-0.7)") (class "Default")
      (node (ref "U10") (pin "41") (pinfunction "0.7_41") (pintype "passive"))
      (node (ref "U7") (pin "14") (pinfunction "DB7_14") (pintype "passive"))
    )
    (net (code "56") (name "Net-(U10-1.0{slash}T2)") (class "Default")
      (node (ref "R12") (pin "2") (pinfunction "2_2") (pintype "passive"))
      (node (ref "U10") (pin "6") (pinfunction "1.0/T2_6") (pintype "passive"))
      (node (ref "U7") (pin "4") (pinfunction "RS_4") (pintype "passive"))
    )
    (net (code "57") (name "Net-(U10-1.1{slash}T2Ex)") (class "Default")
      (node (ref "R13") (pin "2") (pinfunction "2_2") (pintype "passive"))
      (node (ref "U10") (pin "7") (pinfunction "1.1/T2Ex_7") (pintype "passive"))
      (node (ref "U7") (pin "5") (pinfunction "R/~{W}_5") (pintype "passive"))
    )
    (net (code "58") (name "Net-(U10-1.2)") (class "Default")
      (node (ref "R14") (pin "2") (pinfunction "2_2") (pintype "passive"))
      (node (ref "U10") (pin "8") (pinfunction "1.2_8") (pintype "passive"))
      (node (ref "U7") (pin "6") (pinfunction "E_6") (pintype "passive"))
    )
    (net (code "59") (name "Net-(U10-3.4{slash}T0)") (class "Default")
      (node (ref "U10") (pin "20") (pinfunction "3.4/T0_20") (pintype "passive"))
      (node (ref "U15") (pin "3") (pinfunction "OUT_3") (pintype "passive"))
    )
    (net (code "60") (name "Net-(U15-GND)") (class "Default")
      (node (ref "U10") (pin "22") (pinfunction "Gnd_22") (pintype "passive"))
      (node (ref "U15") (pin "2") (pinfunction "GND_2") (pintype "passive"))
    )
    (net (code "61") (name "Net-(U18-1IN-)") (class "Default")
      (node (ref "R30") (pin "1") (pinfunction "1_1") (pintype "passive"))
      (node (ref "R31") (pin "1") (pinfunction "1_1") (pintype "passive"))
      (node (ref "U18") (pin "2") (pinfunction "1IN-_2") (pintype "passive"))
    )
    (net (code "62") (name "Net-(U18-1OUT)") (class "Default")
      (node (ref "R31") (pin "2") (pinfunction "2_2") (pintype "passive"))
      (node (ref "R33") (pin "2") (pinfunction "2_2") (pintype "passive"))
      (node (ref "U18") (pin "1") (pinfunction "1OUT_1") (pintype "passive"))
    )
    (net (code "63") (name "Net-(U18-2N+)") (class "Default")
      (node (ref "R33") (pin "1") (pinfunction "1_1") (pintype "passive"))
      (node (ref "R34") (pin "2") (pinfunction "2_2") (pintype "passive"))
      (node (ref "U18") (pin "5") (pinfunction "2N+_5") (pintype "passive"))
    )
    (net (code "64") (name "Net-(U18-2N-)") (class "Default")
      (node (ref "R32") (pin "2") (pinfunction "2_2") (pintype "passive"))
      (node (ref "R35") (pin "1") (pinfunction "1_1") (pintype "passive"))
      (node (ref "U18") (pin "6") (pinfunction "2N-_6") (pintype "passive"))
    )
    (net (code "65") (name "unconnected-(U1-NC-Pad1)") (class "Default")
      (node (ref "U1") (pin "1") (pinfunction "NC_1") (pintype "passive"))
    )
    (net (code "66") (name "unconnected-(U1-NC-Pad7)") (class "Default")
      (node (ref "U1") (pin "7") (pinfunction "NC_7") (pintype "passive"))
    )
    (net (code "67") (name "unconnected-(U1-NC-Pad8)") (class "Default")
      (node (ref "U1") (pin "8") (pinfunction "NC_8") (pintype "passive"))
    )
    (net (code "68") (name "unconnected-(U1-Temp-Pad3)") (class "Default")
      (node (ref "U1") (pin "3") (pinfunction "Temp_3") (pintype "passive"))
    )
    (net (code "69") (name "unconnected-(U2-NC-Pad1)") (class "Default")
      (node (ref "U2") (pin "1") (pinfunction "NC_1") (pintype "passive"))
    )
    (net (code "70") (name "unconnected-(U2-NC-Pad7)") (class "Default")
      (node (ref "U2") (pin "7") (pinfunction "NC_7") (pintype "passive"))
    )
    (net (code "71") (name "unconnected-(U2-NC-Pad8)") (class "Default")
      (node (ref "U2") (pin "8") (pinfunction "NC_8") (pintype "passive"))
    )
    (net (code "72") (name "unconnected-(U2-Temp-Pad3)") (class "Default")
      (node (ref "U2") (pin "3") (pinfunction "Temp_3") (pintype "passive"))
    )
    (net (code "73") (name "unconnected-(U10-1.7-Pad13)") (class "Default")
      (node (ref "U10") (pin "13") (pinfunction "1.7_13") (pintype "passive"))
    )
    (net (code "74") (name "unconnected-(U10-3.3V-Pad24)") (class "Default")
      (node (ref "U10") (pin "24") (pinfunction "3.3V_24") (pintype "passive"))
    )
    (net (code "75") (name "unconnected-(U10-3.5{slash}T1-Pad21)") (class "Default")
      (node (ref "U10") (pin "21") (pinfunction "3.5/T1_21") (pintype "passive"))
    )
    (net (code "76") (name "unconnected-(U10-4.1-Pad39)") (class "Default")
      (node (ref "U10") (pin "39") (pinfunction "4.1_39") (pintype "passive"))
    )
    (net (code "77") (name "unconnected-(U10-4.2{slash}~{INT3}-Pad5)") (class "Default")
      (node (ref "U10") (pin "5") (pinfunction "4.2/~{INT3}_5") (pintype "passive"))
    )
    (net (code "78") (name "unconnected-(U10-4.3{slash}~{INT2}-Pad16)") (class "Default")
      (node (ref "U10") (pin "16") (pinfunction "4.3/~{INT2}_16") (pintype "passive"))
    )
    (net (code "79") (name "unconnected-(U10-ALE{slash}4.5-Pad38)") (class "Default")
      (node (ref "U10") (pin "38") (pinfunction "ALE/4.5_38") (pintype "passive"))
    )
    (net (code "80") (name "unconnected-(U10-Reset-Pad14)") (class "Default")
      (node (ref "U10") (pin "14") (pinfunction "Reset_14") (pintype "passive"))
    )
    (net (code "81") (name "unconnected-(U10-~{EA}{slash}4.6-Pad40)") (class "Default")
      (node (ref "U10") (pin "40") (pinfunction "~{EA}/4.6_40") (pintype "passive"))
    )
    (net (code "82") (name "unconnected-(U10-~{PSEN}{slash}4.4-Pad37)") (class "Default")
      (node (ref "U10") (pin "37") (pinfunction "~{PSEN}/4.4_37") (pintype "passive"))
    )
    (net (code "83") (name "unconnected-(U10-~{RD}{slash}3.7-Pad27)") (class "Default")
      (node (ref "U10") (pin "27") (pinfunction "~{RD}/3.7_27") (pintype "passive"))
    )
    (net (code "84") (name "unconnected-(U10-~{WR}{slash}3.6-Pad26)") (class "Default")
      (node (ref "U10") (pin "26") (pinfunction "~{WR}/3.6_26") (pintype "passive"))
    )
  )
)
